# Sheet.net
KiCad netlist of a schematic drawn in Altium Designer
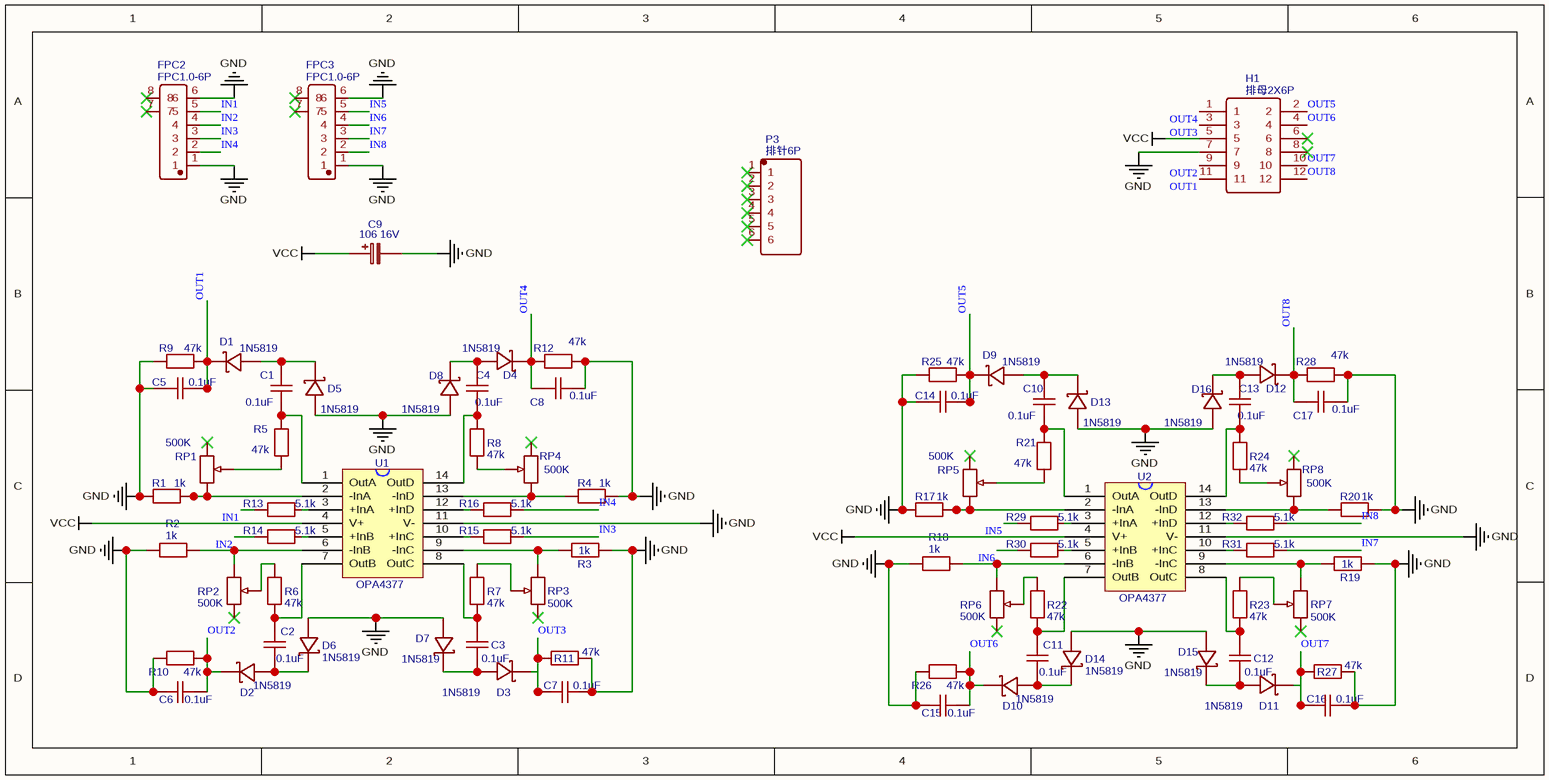
[diagram p0: Sheet_运放.schdoc]

(export (version "E")
  (design (tool "Eeschema 10.0.6"))
  (components
    (comp (ref "C1")
      (value "0.1uF")
      (fields (field (name "CONTRIBUTOR") "LCEDA_Lib"))
      (libsource (lib "altium-import") (part "root_1_0.1uF_"))
    )
    (comp (ref "C2")
      (value "0.1uF")
      (fields (field (name "CONTRIBUTOR") "LCEDA_Lib"))
      (libsource (lib "altium-import") (part "root_1_0.1uF_"))
    )
    (comp (ref "C3")
      (value "0.1uF")
      (fields (field (name "CONTRIBUTOR") "LCEDA_Lib"))
      (libsource (lib "altium-import") (part "root_1_0.1uF_"))
    )
    (comp (ref "C4")
      (value "0.1uF")
      (fields (field (name "CONTRIBUTOR") "LCEDA_Lib"))
      (libsource (lib "altium-import") (part "root_1_0.1uF_"))
    )
    (comp (ref "C5")
      (value "0.1uF")
      (fields (field (name "CONTRIBUTOR") "LCEDA_Lib"))
      (libsource (lib "altium-import") (part "root_2_0.1uF_"))
    )
    (comp (ref "C6")
      (value "0.1uF")
      (fields (field (name "CONTRIBUTOR") "LCEDA_Lib"))
      (libsource (lib "altium-import") (part "root_2_0.1uF_"))
    )
    (comp (ref "C7")
      (value "0.1uF")
      (fields (field (name "CONTRIBUTOR") "LCEDA_Lib"))
      (libsource (lib "altium-import") (part "root_2_0.1uF_"))
    )
    (comp (ref "C8")
      (value "0.1uF")
      (fields (field (name "CONTRIBUTOR") "LCEDA_Lib"))
      (libsource (lib "altium-import") (part "root_2_0.1uF_"))
    )
    (comp (ref "C9")
      (value "106 16V")
      (fields (field (name "CONTRIBUTOR") "LCEDA_Lib"))
      (libsource (lib "altium-import") (part "root_0_106 16V_"))
    )
    (comp (ref "C10")
      (value "0.1uF")
      (fields (field (name "CONTRIBUTOR") "LCEDA_Lib"))
      (libsource (lib "altium-import") (part "root_1_0.1uF_"))
    )
    (comp (ref "C11")
      (value "0.1uF")
      (fields (field (name "CONTRIBUTOR") "LCEDA_Lib"))
      (libsource (lib "altium-import") (part "root_1_0.1uF_"))
    )
    (comp (ref "C12")
      (value "0.1uF")
      (fields (field (name "CONTRIBUTOR") "LCEDA_Lib"))
      (libsource (lib "altium-import") (part "root_1_0.1uF_"))
    )
    (comp (ref "C13")
      (value "0.1uF")
      (fields (field (name "CONTRIBUTOR") "LCEDA_Lib"))
      (libsource (lib "altium-import") (part "root_1_0.1uF_"))
    )
    (comp (ref "C14")
      (value "0.1uF")
      (fields (field (name "CONTRIBUTOR") "LCEDA_Lib"))
      (libsource (lib "altium-import") (part "root_2_0.1uF_"))
    )
    (comp (ref "C15")
      (value "0.1uF")
      (fields (field (name "CONTRIBUTOR") "LCEDA_Lib"))
      (libsource (lib "altium-import") (part "root_2_0.1uF_"))
    )
    (comp (ref "C16")
      (value "0.1uF")
      (fields (field (name "CONTRIBUTOR") "LCEDA_Lib"))
      (libsource (lib "altium-import") (part "root_2_0.1uF_"))
    )
    (comp (ref "C17")
      (value "0.1uF")
      (fields (field (name "CONTRIBUTOR") "LCEDA_Lib"))
      (libsource (lib "altium-import") (part "root_2_0.1uF_"))
    )
    (comp (ref "D1")
      (value "1N5819")
      (fields (field (name "MANUFACTURER") "STMicroelectronics"))
      (libsource (lib "altium-import") (part "root_0_1N5819_"))
    )
    (comp (ref "D2")
      (value "1N5819")
      (fields (field (name "MANUFACTURER") "STMicroelectronics"))
      (libsource (lib "altium-import") (part "root_0_1N5819_"))
    )
    (comp (ref "D3")
      (value "1N5819")
      (fields (field (name "MANUFACTURER") "STMicroelectronics"))
      (libsource (lib "altium-import") (part "root_2_1N5819_"))
    )
    (comp (ref "D4")
      (value "1N5819")
      (fields (field (name "MANUFACTURER") "STMicroelectronics"))
      (libsource (lib "altium-import") (part "root_2_1N5819_"))
    )
    (comp (ref "D5")
      (value "1N5819")
      (fields (field (name "MANUFACTURER") "STMicroelectronics"))
      (libsource (lib "altium-import") (part "root_3_1N5819_"))
    )
    (comp (ref "D6")
      (value "1N5819")
      (fields (field (name "MANUFACTURER") "STMicroelectronics"))
      (libsource (lib "altium-import") (part "root_1_1N5819_"))
    )
    (comp (ref "D7")
      (value "1N5819")
      (fields (field (name "MANUFACTURER") "STMicroelectronics"))
      (libsource (lib "altium-import") (part "root_1_1N5819_"))
    )
    (comp (ref "D8")
      (value "1N5819")
      (fields (field (name "MANUFACTURER") "STMicroelectronics"))
      (libsource (lib "altium-import") (part "root_3_1N5819_"))
    )
    (comp (ref "D9")
      (value "1N5819")
      (fields (field (name "MANUFACTURER") "STMicroelectronics"))
      (libsource (lib "altium-import") (part "root_0_1N5819_"))
    )
    (comp (ref "D10")
      (value "1N5819")
      (fields (field (name "MANUFACTURER") "STMicroelectronics"))
      (libsource (lib "altium-import") (part "root_0_1N5819_"))
    )
    (comp (ref "D11")
      (value "1N5819")
      (fields (field (name "MANUFACTURER") "STMicroelectronics"))
      (libsource (lib "altium-import") (part "root_2_1N5819_"))
    )
    (comp (ref "D12")
      (value "1N5819")
      (fields (field (name "MANUFACTURER") "STMicroelectronics"))
      (libsource (lib "altium-import") (part "root_2_1N5819_"))
    )
    (comp (ref "D13")
      (value "1N5819")
      (fields (field (name "MANUFACTURER") "STMicroelectronics"))
      (libsource (lib "altium-import") (part "root_3_1N5819_"))
    )
    (comp (ref "D14")
      (value "1N5819")
      (fields (field (name "MANUFACTURER") "STMicroelectronics"))
      (libsource (lib "altium-import") (part "root_1_1N5819_"))
    )
    (comp (ref "D15")
      (value "1N5819")
      (fields (field (name "MANUFACTURER") "STMicroelectronics"))
      (libsource (lib "altium-import") (part "root_1_1N5819_"))
    )
    (comp (ref "D16")
      (value "1N5819")
      (fields (field (name "MANUFACTURER") "STMicroelectronics"))
      (libsource (lib "altium-import") (part "root_3_1N5819_"))
    )
    (comp (ref "FPC2")
      (value "FPC1.0-6P")
      (fields
        (field (name "MANUFACTURER") "Ckmtw")
        (field (name "MANUFACTURER PART") "FPC1.0-8P")
        (field (name "CONTRIBUTOR") "zjw101016")
      )
      (libsource (lib "altium-import") (part "root_2_FPC1.0-6P_"))
    )
    (comp (ref "FPC3")
      (value "FPC1.0-6P")
      (fields
        (field (name "MANUFACTURER") "Ckmtw")
        (field (name "MANUFACTURER PART") "FPC1.0-8P")
        (field (name "CONTRIBUTOR") "zjw101016")
      )
      (libsource (lib "altium-import") (part "root_2_FPC1.0-6P_"))
    )
    (comp (ref "H1")
      (value "排母2X6P")
      (fields (field (name "MANUFACTURER") "Shenzhen Cankemeng") (field (name "CONTRIBUTOR") "keying"))
      (libsource (lib "altium-import") (part "root_0_排母2X6P_"))
    )
    (comp (ref "P3")
      (value "排针6P")
      (fields (field (name "CONTRIBUTOR") "qq312022172"))
      (libsource (lib "altium-import") (part "root_0_排针6P_"))
    )
    (comp (ref "R1")
      (value "1k")
      (fields (field (name "CONTRIBUTOR") "LCEDA_Lib"))
      (libsource (lib "altium-import") (part "root_2_1k_"))
    )
    (comp (ref "R2")
      (value "1k")
      (fields (field (name "CONTRIBUTOR") "LCEDA_Lib"))
      (libsource (lib "altium-import") (part "root_0_1k_"))
    )
    (comp (ref "R3")
      (value "1k")
      (fields (field (name "CONTRIBUTOR") "LCEDA_Lib"))
      (libsource (lib "altium-import") (part "root_2_1k_"))
    )
    (comp (ref "R4")
      (value "1k")
      (fields (field (name "CONTRIBUTOR") "LCEDA_Lib"))
      (libsource (lib "altium-import") (part "root_2_1k_"))
    )
    (comp (ref "R5")
      (value "47k")
      (fields (field (name "CONTRIBUTOR") "LCEDA_Lib"))
      (libsource (lib "altium-import") (part "root_1_47k_"))
    )
    (comp (ref "R6")
      (value "47k")
      (fields (field (name "CONTRIBUTOR") "LCEDA_Lib"))
      (libsource (lib "altium-import") (part "root_1_47k_"))
    )
    (comp (ref "R7")
      (value "47k")
      (fields (field (name "CONTRIBUTOR") "LCEDA_Lib"))
      (libsource (lib "altium-import") (part "root_1_47k_"))
    )
    (comp (ref "R8")
      (value "47k")
      (fields (field (name "CONTRIBUTOR") "LCEDA_Lib"))
      (libsource (lib "altium-import") (part "root_3_47k_"))
    )
    (comp (ref "R9")
      (value "47k")
      (fields (field (name "CONTRIBUTOR") "LCEDA_Lib"))
      (libsource (lib "altium-import") (part "root_0_47k_"))
    )
    (comp (ref "R10")
      (value "47k")
      (fields (field (name "CONTRIBUTOR") "LCEDA_Lib"))
      (libsource (lib "altium-import") (part "root_0_47k_"))
    )
    (comp (ref "R11")
      (value "47k")
      (fields (field (name "CONTRIBUTOR") "LCEDA_Lib"))
      (libsource (lib "altium-import") (part "root_0_47k_"))
    )
    (comp (ref "R12")
      (value "47k")
      (fields (field (name "CONTRIBUTOR") "LCEDA_Lib"))
      (libsource (lib "altium-import") (part "root_0_47k_"))
    )
    (comp (ref "R13")
      (value "5.1k")
      (fields (field (name "CONTRIBUTOR") "LCEDA_Lib"))
      (libsource (lib "altium-import") (part "root_0_5.1k_"))
    )
    (comp (ref "R14")
      (value "5.1k")
      (fields (field (name "CONTRIBUTOR") "LCEDA_Lib"))
      (libsource (lib "altium-import") (part "root_0_5.1k_"))
    )
    (comp (ref "R15")
      (value "5.1k")
      (fields (field (name "CONTRIBUTOR") "LCEDA_Lib"))
      (libsource (lib "altium-import") (part "root_0_5.1k_"))
    )
    (comp (ref "R16")
      (value "5.1k")
      (fields (field (name "CONTRIBUTOR") "LCEDA_Lib"))
      (libsource (lib "altium-import") (part "root_0_5.1k_"))
    )
    (comp (ref "R17")
      (value "1k")
      (fields (field (name "CONTRIBUTOR") "LCEDA_Lib"))
      (libsource (lib "altium-import") (part "root_2_1k_"))
    )
    (comp (ref "R18")
      (value "1k")
      (fields (field (name "CONTRIBUTOR") "LCEDA_Lib"))
      (libsource (lib "altium-import") (part "root_0_1k_"))
    )
    (comp (ref "R19")
      (value "1k")
      (fields (field (name "CONTRIBUTOR") "LCEDA_Lib"))
      (libsource (lib "altium-import") (part "root_2_1k_"))
    )
    (comp (ref "R20")
      (value "1k")
      (fields (field (name "CONTRIBUTOR") "LCEDA_Lib"))
      (libsource (lib "altium-import") (part "root_2_1k_"))
    )
    (comp (ref "R21")
      (value "47k")
      (fields (field (name "CONTRIBUTOR") "LCEDA_Lib"))
      (libsource (lib "altium-import") (part "root_1_47k_"))
    )
    (comp (ref "R22")
      (value "47k")
      (fields (field (name "CONTRIBUTOR") "LCEDA_Lib"))
      (libsource (lib "altium-import") (part "root_1_47k_"))
    )
    (comp (ref "R23")
      (value "47k")
      (fields (field (name "CONTRIBUTOR") "LCEDA_Lib"))
      (libsource (lib "altium-import") (part "root_1_47k_"))
    )
    (comp (ref "R24")
      (value "47k")
      (fields (field (name "CONTRIBUTOR") "LCEDA_Lib"))
      (libsource (lib "altium-import") (part "root_3_47k_"))
    )
    (comp (ref "R25")
      (value "47k")
      (fields (field (name "CONTRIBUTOR") "LCEDA_Lib"))
      (libsource (lib "altium-import") (part "root_0_47k_"))
    )
    (comp (ref "R26")
      (value "47k")
      (fields (field (name "CONTRIBUTOR") "LCEDA_Lib"))
      (libsource (lib "altium-import") (part "root_0_47k_"))
    )
    (comp (ref "R27")
      (value "47k")
      (fields (field (name "CONTRIBUTOR") "LCEDA_Lib"))
      (libsource (lib "altium-import") (part "root_0_47k_"))
    )
    (comp (ref "R28")
      (value "47k")
      (fields (field (name "CONTRIBUTOR") "LCEDA_Lib"))
      (libsource (lib "altium-import") (part "root_0_47k_"))
    )
    (comp (ref "R29")
      (value "5.1k")
      (fields (field (name "CONTRIBUTOR") "LCEDA_Lib"))
      (libsource (lib "altium-import") (part "root_0_5.1k_"))
    )
    (comp (ref "R30")
      (value "5.1k")
      (fields (field (name "CONTRIBUTOR") "LCEDA_Lib"))
      (libsource (lib "altium-import") (part "root_0_5.1k_"))
    )
    (comp (ref "R31")
      (value "5.1k")
      (fields (field (name "CONTRIBUTOR") "LCEDA_Lib"))
      (libsource (lib "altium-import") (part "root_0_5.1k_"))
    )
    (comp (ref "R32")
      (value "5.1k")
      (fields (field (name "CONTRIBUTOR") "LCEDA_Lib"))
      (libsource (lib "altium-import") (part "root_0_5.1k_"))
    )
    (comp (ref "RP1")
      (value "500K")
      (fields (field (name "CONTRIBUTOR") "LCEDA_Lib"))
      (libsource (lib "altium-import") (part "root_3_500K_"))
    )
    (comp (ref "RP2")
      (value "500K")
      (fields (field (name "CONTRIBUTOR") "LCEDA_Lib"))
      (libsource (lib "altium-import") (part "root_3_500K_"))
    )
    (comp (ref "RP3")
      (value "500K")
      (fields (field (name "CONTRIBUTOR") "LCEDA_Lib"))
      (libsource (lib "altium-import") (part "root_1_500K_"))
    )
    (comp (ref "RP4")
      (value "500K")
      (fields (field (name "CONTRIBUTOR") "LCEDA_Lib"))
      (libsource (lib "altium-import") (part "root_1_500K_"))
    )
    (comp (ref "RP5")
      (value "500K")
      (fields (field (name "CONTRIBUTOR") "LCEDA_Lib"))
      (libsource (lib "altium-import") (part "root_3_500K_"))
    )
    (comp (ref "RP6")
      (value "500K")
      (fields (field (name "CONTRIBUTOR") "LCEDA_Lib"))
      (libsource (lib "altium-import") (part "root_3_500K_"))
    )
    (comp (ref "RP7")
      (value "500K")
      (fields (field (name "CONTRIBUTOR") "LCEDA_Lib"))
      (libsource (lib "altium-import") (part "root_1_500K_"))
    )
    (comp (ref "RP8")
      (value "500K")
      (fields (field (name "CONTRIBUTOR") "LCEDA_Lib"))
      (libsource (lib "altium-import") (part "root_1_500K_"))
    )
    (comp (ref "U1")
      (value "OPA4377")
      (fields (field (name "CONTRIBUTOR") "Adventurex"))
      (libsource (lib "altium-import") (part "root_0_OPA4377_"))
    )
    (comp (ref "U2")
      (value "OPA4377")
      (fields (field (name "CONTRIBUTOR") "Adventurex"))
      (libsource (lib "altium-import") (part "root_0_OPA4377_"))
    )
  )
  (nets
    (net (code "1") (name "/IN1") (class "Default")
      (node (ref "FPC2") (pin "5") (pinfunction "5_5") (pintype "passive"))
      (node (ref "R13") (pin "1") (pinfunction "1_1") (pintype "passive"))
    )
    (net (code "2") (name "/IN2") (class "Default")
      (node (ref "FPC2") (pin "4") (pinfunction "4_4") (pintype "passive"))
      (node (ref "R14") (pin "1") (pinfunction "1_1") (pintype "passive"))
    )
    (net (code "3") (name "/IN3") (class "Default")
      (node (ref "FPC2") (pin "3") (pinfunction "3_3") (pintype "passive"))
      (node (ref "R15") (pin "2") (pinfunction "2_2") (pintype "passive"))
    )
    (net (code "4") (name "/IN4") (class "Default")
      (node (ref "FPC2") (pin "2") (pinfunction "2_2") (pintype "passive"))
      (node (ref "R16") (pin "2") (pinfunction "2_2") (pintype "passive"))
    )
    (net (code "5") (name "/IN5") (class "Default")
      (node (ref "FPC3") (pin "5") (pinfunction "5_5") (pintype "passive"))
      (node (ref "R29") (pin "1") (pinfunction "1_1") (pintype "passive"))
    )
    (net (code "6") (name "/IN6") (class "Default")
      (node (ref "FPC3") (pin "4") (pinfunction "4_4") (pintype "passive"))
      (node (ref "R30") (pin "1") (pinfunction "1_1") (pintype "passive"))
    )
    (net (code "7") (name "/IN7") (class "Default")
      (node (ref "FPC3") (pin "3") (pinfunction "3_3") (pintype "passive"))
      (node (ref "R31") (pin "2") (pinfunction "2_2") (pintype "passive"))
    )
    (net (code "8") (name "/IN8") (class "Default")
      (node (ref "FPC3") (pin "2") (pinfunction "2_2") (pintype "passive"))
      (node (ref "R32") (pin "2") (pinfunction "2_2") (pintype "passive"))
    )
    (net (code "9") (name "/OUT1") (class "Default")
      (node (ref "C5") (pin "1") (pinfunction "1_1") (pintype "passive"))
      (node (ref "D1") (pin "2") (pinfunction "K_2") (pintype "passive"))
      (node (ref "H1") (pin "11") (pinfunction "11_11") (pintype "passive"))
      (node (ref "R9") (pin "2") (pinfunction "2_2") (pintype "passive"))
    )
    (net (code "10") (name "/OUT2") (class "Default")
      (node (ref "C6") (pin "1") (pinfunction "1_1") (pintype "passive"))
      (node (ref "D2") (pin "2") (pinfunction "K_2") (pintype "passive"))
      (node (ref "H1") (pin "9") (pinfunction "9_9") (pintype "passive"))
      (node (ref "R10") (pin "2") (pinfunction "2_2") (pintype "passive"))
    )
    (net (code "11") (name "/OUT3") (class "Default")
      (node (ref "C7") (pin "2") (pinfunction "2_2") (pintype "passive"))
      (node (ref "D3") (pin "2") (pinfunction "K_2") (pintype "passive"))
      (node (ref "H1") (pin "3") (pinfunction "3_3") (pintype "passive"))
      (node (ref "R11") (pin "1") (pinfunction "1_1") (pintype "passive"))
    )
    (net (code "12") (name "/OUT4") (class "Default")
      (node (ref "C8") (pin "2") (pinfunction "2_2") (pintype "passive"))
      (node (ref "D4") (pin "2") (pinfunction "K_2") (pintype "passive"))
      (node (ref "H1") (pin "1") (pinfunction "1_1") (pintype "passive"))
      (node (ref "R12") (pin "1") (pinfunction "1_1") (pintype "passive"))
    )
    (net (code "13") (name "/OUT5") (class "Default")
      (node (ref "C14") (pin "1") (pinfunction "1_1") (pintype "passive"))
      (node (ref "D9") (pin "2") (pinfunction "K_2") (pintype "passive"))
      (node (ref "H1") (pin "2") (pinfunction "2_2") (pintype "passive"))
      (node (ref "R25") (pin "2") (pinfunction "2_2") (pintype "passive"))
    )
    (net (code "14") (name "/OUT6") (class "Default")
      (node (ref "C15") (pin "1") (pinfunction "1_1") (pintype "passive"))
      (node (ref "D10") (pin "2") (pinfunction "K_2") (pintype "passive"))
      (node (ref "H1") (pin "4") (pinfunction "4_4") (pintype "passive"))
      (node (ref "R26") (pin "2") (pinfunction "2_2") (pintype "passive"))
    )
    (net (code "15") (name "/OUT7") (class "Default")
      (node (ref "C16") (pin "2") (pinfunction "2_2") (pintype "passive"))
      (node (ref "D11") (pin "2") (pinfunction "K_2") (pintype "passive"))
      (node (ref "H1") (pin "10") (pinfunction "10_10") (pintype "passive"))
      (node (ref "R27") (pin "1") (pinfunction "1_1") (pintype "passive"))
    )
    (net (code "16") (name "/OUT8") (class "Default")
      (node (ref "C17") (pin "2") (pinfunction "2_2") (pintype "passive"))
      (node (ref "D12") (pin "2") (pinfunction "K_2") (pintype "passive"))
      (node (ref "H1") (pin "12") (pinfunction "12_12") (pintype "passive"))
      (node (ref "R28") (pin "1") (pinfunction "1_1") (pintype "passive"))
    )
    (net (code "17") (name "GND") (class "Default")
      (node (ref "C14") (pin "2") (pinfunction "2_2") (pintype "passive"))
      (node (ref "C15") (pin "2") (pinfunction "2_2") (pintype "passive"))
      (node (ref "C16") (pin "1") (pinfunction "1_1") (pintype "passive"))
      (node (ref "C17") (pin "1") (pinfunction "1_1") (pintype "passive"))
      (node (ref "C5") (pin "2") (pinfunction "2_2") (pintype "passive"))
      (node (ref "C6") (pin "2") (pinfunction "2_2") (pintype "passive"))
      (node (ref "C7") (pin "1") (pinfunction "1_1") (pintype "passive"))
      (node (ref "C8") (pin "1") (pinfunction "1_1") (pintype "passive"))
      (node (ref "C9") (pin "2") (pinfunction "2_2") (pintype "passive"))
      (node (ref "D13") (pin "1") (pinfunction "A_1") (pintype "passive"))
      (node (ref "D14") (pin "1") (pinfunction "A_1") (pintype "passive"))
      (node (ref "D15") (pin "1") (pinfunction "A_1") (pintype "passive"))
      (node (ref "D16") (pin "1") (pinfunction "A_1") (pintype "passive"))
      (node (ref "D5") (pin "1") (pinfunction "A_1") (pintype "passive"))
      (node (ref "D6") (pin "1") (pinfunction "A_1") (pintype "passive"))
      (node (ref "D7") (pin "1") (pinfunction "A_1") (pintype "passive"))
      (node (ref "D8") (pin "1") (pinfunction "A_1") (pintype "passive"))
      (node (ref "FPC2") (pin "1") (pinfunction "1_1") (pintype "passive"))
      (node (ref "FPC2") (pin "6") (pinfunction "6_6") (pintype "passive"))
      (node (ref "FPC3") (pin "1") (pinfunction "1_1") (pintype "passive"))
      (node (ref "FPC3") (pin "6") (pinfunction "6_6") (pintype "passive"))
      (node (ref "H1") (pin "7") (pinfunction "7_7") (pintype "passive"))
      (node (ref "R1") (pin "2") (pinfunction "2_2") (pintype "passive"))
      (node (ref "R10") (pin "1") (pinfunction "1_1") (pintype "passive"))
      (node (ref "R11") (pin "2") (pinfunction "2_2") (pintype "passive"))
      (node (ref "R12") (pin "2") (pinfunction "2_2") (pintype "passive"))
      (node (ref "R17") (pin "2") (pinfunction "2_2") (pintype "passive"))
      (node (ref "R18") (pin "1") (pinfunction "1_1") (pintype "passive"))
      (node (ref "R19") (pin "1") (pinfunction "1_1") (pintype "passive"))
      (node (ref "R2") (pin "1") (pinfunction "1_1") (pintype "passive"))
      (node (ref "R20") (pin "1") (pinfunction "1_1") (pintype "passive"))
      (node (ref "R25") (pin "1") (pinfunction "1_1") (pintype "passive"))
      (node (ref "R26") (pin "1") (pinfunction "1_1") (pintype "passive"))
      (node (ref "R27") (pin "2") (pinfunction "2_2") (pintype "passive"))
      (node (ref "R28") (pin "2") (pinfunction "2_2") (pintype "passive"))
      (node (ref "R3") (pin "1") (pinfunction "1_1") (pintype "passive"))
      (node (ref "R4") (pin "1") (pinfunction "1_1") (pintype "passive"))
      (node (ref "R9") (pin "1") (pinfunction "1_1") (pintype "passive"))
      (node (ref "U1") (pin "11") (pinfunction "V-_11") (pintype "passive"))
      (node (ref "U2") (pin "11") (pinfunction "V-_11") (pintype "passive"))
    )
    (net (code "18") (name "Net-(D1-A)") (class "Default")
      (node (ref "C1") (pin "2") (pinfunction "2_2") (pintype "passive"))
      (node (ref "D1") (pin "1") (pinfunction "A_1") (pintype "passive"))
      (node (ref "D5") (pin "2") (pinfunction "K_2") (pintype "passive"))
    )
    (net (code "19") (name "Net-(D2-A)") (class "Default")
      (node (ref "C2") (pin "1") (pinfunction "1_1") (pintype "passive"))
      (node (ref "D2") (pin "1") (pinfunction "A_1") (pintype "passive"))
      (node (ref "D6") (pin "2") (pinfunction "K_2") (pintype "passive"))
    )
    (net (code "20") (name "Net-(D3-A)") (class "Default")
      (node (ref "C3") (pin "1") (pinfunction "1_1") (pintype "passive"))
      (node (ref "D3") (pin "1") (pinfunction "A_1") (pintype "passive"))
      (node (ref "D7") (pin "2") (pinfunction "K_2") (pintype "passive"))
    )
    (net (code "21") (name "Net-(D4-A)") (class "Default")
      (node (ref "C4") (pin "2") (pinfunction "2_2") (pintype "passive"))
      (node (ref "D4") (pin "1") (pinfunction "A_1") (pintype "passive"))
      (node (ref "D8") (pin "2") (pinfunction "K_2") (pintype "passive"))
    )
    (net (code "22") (name "Net-(D10-A)") (class "Default")
      (node (ref "C11") (pin "1") (pinfunction "1_1") (pintype "passive"))
      (node (ref "D10") (pin "1") (pinfunction "A_1") (pintype "passive"))
      (node (ref "D14") (pin "2") (pinfunction "K_2") (pintype "passive"))
    )
    (net (code "23") (name "Net-(D11-A)") (class "Default")
      (node (ref "C12") (pin "1") (pinfunction "1_1") (pintype "passive"))
      (node (ref "D11") (pin "1") (pinfunction "A_1") (pintype "passive"))
      (node (ref "D15") (pin "2") (pinfunction "K_2") (pintype "passive"))
    )
    (net (code "24") (name "Net-(D12-A)") (class "Default")
      (node (ref "C13") (pin "2") (pinfunction "2_2") (pintype "passive"))
      (node (ref "D12") (pin "1") (pinfunction "A_1") (pintype "passive"))
      (node (ref "D16") (pin "2") (pinfunction "K_2") (pintype "passive"))
    )
    (net (code "25") (name "Net-(D13-K)") (class "Default")
      (node (ref "C10") (pin "2") (pinfunction "2_2") (pintype "passive"))
      (node (ref "D13") (pin "2") (pinfunction "K_2") (pintype "passive"))
      (node (ref "D9") (pin "1") (pinfunction "A_1") (pintype "passive"))
    )
    (net (code "26") (name "Net-(R5-Pad1)") (class "Default")
      (node (ref "R5") (pin "1") (pinfunction "1_1") (pintype "passive"))
      (node (ref "RP1") (pin "2") (pinfunction "2_2") (pintype "passive"))
    )
    (net (code "27") (name "Net-(R6-Pad2)") (class "Default")
      (node (ref "R6") (pin "2") (pinfunction "2_2") (pintype "passive"))
      (node (ref "RP2") (pin "2") (pinfunction "2_2") (pintype "passive"))
    )
    (net (code "28") (name "Net-(R7-Pad2)") (class "Default")
      (node (ref "R7") (pin "2") (pinfunction "2_2") (pintype "passive"))
      (node (ref "RP3") (pin "2") (pinfunction "2_2") (pintype "passive"))
    )
    (net (code "29") (name "Net-(R8-Pad2)") (class "Default")
      (node (ref "R8") (pin "2") (pinfunction "2_2") (pintype "passive"))
      (node (ref "RP4") (pin "2") (pinfunction "2_2") (pintype "passive"))
    )
    (net (code "30") (name "Net-(R21-Pad1)") (class "Default")
      (node (ref "R21") (pin "1") (pinfunction "1_1") (pintype "passive"))
      (node (ref "RP5") (pin "2") (pinfunction "2_2") (pintype "passive"))
    )
    (net (code "31") (name "Net-(R22-Pad2)") (class "Default")
      (node (ref "R22") (pin "2") (pinfunction "2_2") (pintype "passive"))
      (node (ref "RP6") (pin "2") (pinfunction "2_2") (pintype "passive"))
    )
    (net (code "32") (name "Net-(R23-Pad2)") (class "Default")
      (node (ref "R23") (pin "2") (pinfunction "2_2") (pintype "passive"))
      (node (ref "RP7") (pin "2") (pinfunction "2_2") (pintype "passive"))
    )
    (net (code "33") (name "Net-(R24-Pad2)") (class "Default")
      (node (ref "R24") (pin "2") (pinfunction "2_2") (pintype "passive"))
      (node (ref "RP8") (pin "2") (pinfunction "2_2") (pintype "passive"))
    )
    (net (code "34") (name "Net-(U1-+InA)") (class "Default")
      (node (ref "R13") (pin "2") (pinfunction "2_2") (pintype "passive"))
      (node (ref "U1") (pin "3") (pinfunction "+InA_3") (pintype "passive"))
    )
    (net (code "35") (name "Net-(U1-+InB)") (class "Default")
      (node (ref "R14") (pin "2") (pinfunction "2_2") (pintype "passive"))
      (node (ref "U1") (pin "5") (pinfunction "+InB_5") (pintype "passive"))
    )
    (net (code "36") (name "Net-(U1-+InC)") (class "Default")
      (node (ref "R15") (pin "1") (pinfunction "1_1") (pintype "passive"))
      (node (ref "U1") (pin "10") (pinfunction "+InC_10") (pintype "passive"))
    )
    (net (code "37") (name "Net-(U1-+InD)") (class "Default")
      (node (ref "R16") (pin "1") (pinfunction "1_1") (pintype "passive"))
      (node (ref "U1") (pin "12") (pinfunction "+InD_12") (pintype "passive"))
    )
    (net (code "38") (name "Net-(U1--InA)") (class "Default")
      (node (ref "R1") (pin "1") (pinfunction "1_1") (pintype "passive"))
      (node (ref "RP1") (pin "3") (pinfunction "3_3") (pintype "passive"))
      (node (ref "U1") (pin "2") (pinfunction "-InA_2") (pintype "passive"))
    )
    (net (code "39") (name "Net-(U1--InB)") (class "Default")
      (node (ref "R2") (pin "2") (pinfunction "2_2") (pintype "passive"))
      (node (ref "RP2") (pin "1") (pinfunction "1_1") (pintype "passive"))
      (node (ref "U1") (pin "6") (pinfunction "-InB_6") (pintype "passive"))
    )
    (net (code "40") (name "Net-(U1--InC)") (class "Default")
      (node (ref "R3") (pin "2") (pinfunction "2_2") (pintype "passive"))
      (node (ref "RP3") (pin "3") (pinfunction "3_3") (pintype "passive"))
      (node (ref "U1") (pin "9") (pinfunction "-InC_9") (pintype "passive"))
    )
    (net (code "41") (name "Net-(U1--InD)") (class "Default")
      (node (ref "R4") (pin "2") (pinfunction "2_2") (pintype "passive"))
      (node (ref "RP4") (pin "1") (pinfunction "1_1") (pintype "passive"))
      (node (ref "U1") (pin "13") (pinfunction "-InD_13") (pintype "passive"))
    )
    (net (code "42") (name "Net-(U1-OutA)") (class "Default")
      (node (ref "C1") (pin "1") (pinfunction "1_1") (pintype "passive"))
      (node (ref "R5") (pin "2") (pinfunction "2_2") (pintype "passive"))
      (node (ref "U1") (pin "1") (pinfunction "OutA_1") (pintype "passive"))
    )
    (net (code "43") (name "Net-(U1-OutB)") (class "Default")
      (node (ref "C2") (pin "2") (pinfunction "2_2") (pintype "passive"))
      (node (ref "R6") (pin "1") (pinfunction "1_1") (pintype "passive"))
      (node (ref "U1") (pin "7") (pinfunction "OutB_7") (pintype "passive"))
    )
    (net (code "44") (name "Net-(U1-OutC)") (class "Default")
      (node (ref "C3") (pin "2") (pinfunction "2_2") (pintype "passive"))
      (node (ref "R7") (pin "1") (pinfunction "1_1") (pintype "passive"))
      (node (ref "U1") (pin "8") (pinfunction "OutC_8") (pintype "passive"))
    )
    (net (code "45") (name "Net-(U1-OutD)") (class "Default")
      (node (ref "C4") (pin "1") (pinfunction "1_1") (pintype "passive"))
      (node (ref "R8") (pin "1") (pinfunction "1_1") (pintype "passive"))
      (node (ref "U1") (pin "14") (pinfunction "OutD_14") (pintype "passive"))
    )
    (net (code "46") (name "Net-(U2-+InA)") (class "Default")
      (node (ref "R29") (pin "2") (pinfunction "2_2") (pintype "passive"))
      (node (ref "U2") (pin "3") (pinfunction "+InA_3") (pintype "passive"))
    )
    (net (code "47") (name "Net-(U2-+InB)") (class "Default")
      (node (ref "R30") (pin "2") (pinfunction "2_2") (pintype "passive"))
      (node (ref "U2") (pin "5") (pinfunction "+InB_5") (pintype "passive"))
    )
    (net (code "48") (name "Net-(U2-+InC)") (class "Default")
      (node (ref "R31") (pin "1") (pinfunction "1_1") (pintype "passive"))
      (node (ref "U2") (pin "10") (pinfunction "+InC_10") (pintype "passive"))
    )
    (net (code "49") (name "Net-(U2-+InD)") (class "Default")
      (node (ref "R32") (pin "1") (pinfunction "1_1") (pintype "passive"))
      (node (ref "U2") (pin "12") (pinfunction "+InD_12") (pintype "passive"))
    )
    (net (code "50") (name "Net-(U2--InA)") (class "Default")
      (node (ref "R17") (pin "1") (pinfunction "1_1") (pintype "passive"))
      (node (ref "RP5") (pin "3") (pinfunction "3_3") (pintype "passive"))
      (node (ref "U2") (pin "2") (pinfunction "-InA_2") (pintype "passive"))
    )
    (net (code "51") (name "Net-(U2--InB)") (class "Default")
      (node (ref "R18") (pin "2") (pinfunction "2_2") (pintype "passive"))
      (node (ref "RP6") (pin "1") (pinfunction "1_1") (pintype "passive"))
      (node (ref "U2") (pin "6") (pinfunction "-InB_6") (pintype "passive"))
    )
    (net (code "52") (name "Net-(U2--InC)") (class "Default")
      (node (ref "R19") (pin "2") (pinfunction "2_2") (pintype "passive"))
      (node (ref "RP7") (pin "3") (pinfunction "3_3") (pintype "passive"))
      (node (ref "U2") (pin "9") (pinfunction "-InC_9") (pintype "passive"))
    )
    (net (code "53") (name "Net-(U2--InD)") (class "Default")
      (node (ref "R20") (pin "2") (pinfunction "2_2") (pintype "passive"))
      (node (ref "RP8") (pin "1") (pinfunction "1_1") (pintype "passive"))
      (node (ref "U2") (pin "13") (pinfunction "-InD_13") (pintype "passive"))
    )
    (net (code "54") (name "Net-(U2-OutA)") (class "Default")
      (node (ref "C10") (pin "1") (pinfunction "1_1") (pintype "passive"))
      (node (ref "R21") (pin "2") (pinfunction "2_2") (pintype "passive"))
      (node (ref "U2") (pin "1") (pinfunction "OutA_1") (pintype "passive"))
    )
    (net (code "55") (name "Net-(U2-OutB)") (class "Default")
      (node (ref "C11") (pin "2") (pinfunction "2_2") (pintype "passive"))
      (node (ref "R22") (pin "1") (pinfunction "1_1") (pintype "passive"))
      (node (ref "U2") (pin "7") (pinfunction "OutB_7") (pintype "passive"))
    )
    (net (code "56") (name "Net-(U2-OutC)") (class "Default")
      (node (ref "C12") (pin "2") (pinfunction "2_2") (pintype "passive"))
      (node (ref "R23") (pin "1") (pinfunction "1_1") (pintype "passive"))
      (node (ref "U2") (pin "8") (pinfunction "OutC_8") (pintype "passive"))
    )
    (net (code "57") (name "Net-(U2-OutD)") (class "Default")
      (node (ref "C13") (pin "1") (pinfunction "1_1") (pintype "passive"))
      (node (ref "R24") (pin "1") (pinfunction "1_1") (pintype "passive"))
      (node (ref "U2") (pin "14") (pinfunction "OutD_14") (pintype "passive"))
    )
    (net (code "58") (name "VCC") (class "Default")
      (node (ref "C9") (pin "1") (pinfunction "1_1") (pintype "passive"))
      (node (ref "H1") (pin "5") (pinfunction "5_5") (pintype "passive"))
      (node (ref "U1") (pin "4") (pinfunction "V+_4") (pintype "passive"))
      (node (ref "U2") (pin "4") (pinfunction "V+_4") (pintype "passive"))
    )
    (net (code "59") (name "unconnected-(FPC2-Pad7)") (class "Default")
      (node (ref "FPC2") (pin "7") (pinfunction "7_7") (pintype "passive+no_connect"))
    )
    (net (code "60") (name "unconnected-(FPC2-Pad8)") (class "Default")
      (node (ref "FPC2") (pin "8") (pinfunction "8_8") (pintype "passive+no_connect"))
    )
    (net (code "61") (name "unconnected-(FPC3-Pad7)") (class "Default")
      (node (ref "FPC3") (pin "7") (pinfunction "7_7") (pintype "passive+no_connect"))
    )
    (net (code "62") (name "unconnected-(FPC3-Pad8)") (class "Default")
      (node (ref "FPC3") (pin "8") (pinfunction "8_8") (pintype "passive+no_connect"))
    )
    (net (code "63") (name "unconnected-(H1-Pad6)") (class "Default")
      (node (ref "H1") (pin "6") (pinfunction "6_6") (pintype "passive+no_connect"))
    )
    (net (code "64") (name "unconnected-(H1-Pad8)") (class "Default")
      (node (ref "H1") (pin "8") (pinfunction "8_8") (pintype "passive+no_connect"))
    )
    (net (code "65") (name "unconnected-(P3-Pad1)") (class "Default")
      (node (ref "P3") (pin "1") (pinfunction "1_1") (pintype "passive+no_connect"))
    )
    (net (code "66") (name "unconnected-(P3-Pad2)") (class "Default")
      (node (ref "P3") (pin "2") (pinfunction "2_2") (pintype "passive+no_connect"))
    )
    (net (code "67") (name "unconnected-(P3-Pad3)") (class "Default")
      (node (ref "P3") (pin "3") (pinfunction "3_3") (pintype "passive+no_connect"))
    )
    (net (code "68") (name "unconnected-(P3-Pad4)") (class "Default")
      (node (ref "P3") (pin "4") (pinfunction "4_4") (pintype "passive+no_connect"))
    )
    (net (code "69") (name "unconnected-(P3-Pad5)") (class "Default")
      (node (ref "P3") (pin "5") (pinfunction "5_5") (pintype "passive+no_connect"))
    )
    (net (code "70") (name "unconnected-(P3-Pad6)") (class "Default")
      (node (ref "P3") (pin "6") (pinfunction "6_6") (pintype "passive+no_connect"))
    )
    (net (code "71") (name "unconnected-(RP1-Pad1)") (class "Default")
      (node (ref "RP1") (pin "1") (pinfunction "1_1") (pintype "passive+no_connect"))
    )
    (net (code "72") (name "unconnected-(RP2-Pad3)") (class "Default")
      (node (ref "RP2") (pin "3") (pinfunction "3_3") (pintype "passive+no_connect"))
    )
    (net (code "73") (name "unconnected-(RP3-Pad1)") (class "Default")
      (node (ref "RP3") (pin "1") (pinfunction "1_1") (pintype "passive+no_connect"))
    )
    (net (code "74") (name "unconnected-(RP4-Pad3)") (class "Default")
      (node (ref "RP4") (pin "3") (pinfunction "3_3") (pintype "passive+no_connect"))
    )
    (net (code "75") (name "unconnected-(RP5-Pad1)") (class "Default")
      (node (ref "RP5") (pin "1") (pinfunction "1_1") (pintype "passive+no_connect"))
    )
    (net (code "76") (name "unconnected-(RP6-Pad3)") (class "Default")
      (node (ref "RP6") (pin "3") (pinfunction "3_3") (pintype "passive+no_connect"))
    )
    (net (code "77") (name "unconnected-(RP7-Pad1)") (class "Default")
      (node (ref "RP7") (pin "1") (pinfunction "1_1") (pintype "passive+no_connect"))
    )
    (net (code "78") (name "unconnected-(RP8-Pad3)") (class "Default")
      (node (ref "RP8") (pin "3") (pinfunction "3_3") (pintype "passive+no_connect"))
    )
  )
)
